# USB-C.net
KiCad netlist of a schematic drawn in Altium Designer
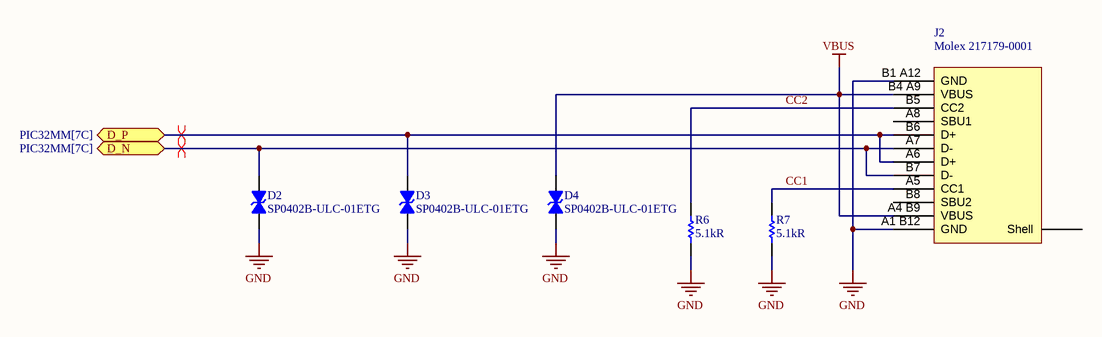
[diagram p0: USB-C.SchDoc]

(export (version "E")
  (design (tool "Eeschema 10.0.6"))
  (components
    (comp (ref "D2")
      (value "SP0402B-ULC-01ETG")
      (footprint "Diode TVS 0402")
      (libsource (lib "x-io") (part "Diode TVS"))
    )
    (comp (ref "D3")
      (value "SP0402B-ULC-01ETG")
      (footprint "Diode TVS 0402")
      (libsource (lib "x-io") (part "Diode TVS"))
    )
    (comp (ref "D4")
      (value "SP0402B-ULC-01ETG")
      (footprint "Diode TVS 0402")
      (libsource (lib "x-io") (part "Diode TVS"))
    )
    (comp (ref "J2")
      (value "Molex 217179-0001")
      (footprint "Molex 217179-0001")
      (libsource (lib "x-io") (part "USB-C Receptacle (16 Pin)"))
    )
    (comp (ref "R6") (value "5.1kR") (footprint "Resistor 0402") (libsource (lib "x-io") (part "Resistor")))
    (comp (ref "R7") (value "5.1kR") (footprint "Resistor 0402") (libsource (lib "x-io") (part "Resistor")))
  )
  (nets
    (net (code "1") (name "/CC1") (class "Default")
      (node (ref "J2") (pin "A5") (pinfunction "CC1_A5") (pintype "passive"))
      (node (ref "R7") (pin "2") (pinfunction "2_2") (pintype "passive"))
    )
    (net (code "2") (name "/CC2") (class "Default")
      (node (ref "J2") (pin "B5") (pinfunction "CC2_B5") (pintype "passive"))
      (node (ref "R6") (pin "2") (pinfunction "2_2") (pintype "passive"))
    )
    (net (code "3") (name "/D_N") (class "Default")
      (node (ref "D2") (pin "1") (pinfunction "*_1") (pintype "passive"))
      (node (ref "J2") (pin "A7") (pinfunction "D-_A7") (pintype "passive"))
      (node (ref "J2") (pin "B7") (pinfunction "D-_B7") (pintype "passive"))
    )
    (net (code "4") (name "/D_P") (class "Default")
      (node (ref "D3") (pin "1") (pinfunction "*_1") (pintype "passive"))
      (node (ref "J2") (pin "A6") (pinfunction "D+_A6") (pintype "passive"))
      (node (ref "J2") (pin "B6") (pinfunction "D+_B6") (pintype "passive"))
    )
    (net (code "5") (name "GND") (class "Default")
      (node (ref "D2") (pin "2") (pinfunction "*_2") (pintype "passive"))
      (node (ref "D3") (pin "2") (pinfunction "*_2") (pintype "passive"))
      (node (ref "D4") (pin "2") (pinfunction "*_2") (pintype "passive"))
      (node (ref "J2") (pin "A1_B12") (pinfunction "GND_A1_B12") (pintype "passive"))
      (node (ref "J2") (pin "B1_A12") (pinfunction "GND_B1_A12") (pintype "passive"))
      (node (ref "R6") (pin "1") (pinfunction "1_1") (pintype "passive"))
      (node (ref "R7") (pin "1") (pinfunction "1_1") (pintype "passive"))
    )
    (net (code "6") (name "VBUS") (class "Default")
      (node (ref "D4") (pin "1") (pinfunction "*_1") (pintype "passive"))
      (node (ref "J2") (pin "A4_B9") (pinfunction "VBUS_A4_B9") (pintype "passive"))
      (node (ref "J2") (pin "B4_A9") (pinfunction "VBUS_B4_A9") (pintype "passive"))
    )
    (net (code "7") (name "unconnected-(J2-PadShell)") (class "Default")
      (node (ref "J2") (pin "Shell") (pinfunction "Shell_Shell") (pintype "passive"))
    )
    (net (code "8") (name "unconnected-(J2-SBU1-PadA8)") (class "Default")
      (node (ref "J2") (pin "A8") (pinfunction "SBU1_A8") (pintype "passive"))
    )
    (net (code "9") (name "unconnected-(J2-SBU2-PadB8)") (class "Default")
      (node (ref "J2") (pin "B8") (pinfunction "SBU2_B8") (pintype "passive"))
    )
  )
)
